# Extruder.net
KiCad netlist of a schematic drawn in Altium Designer
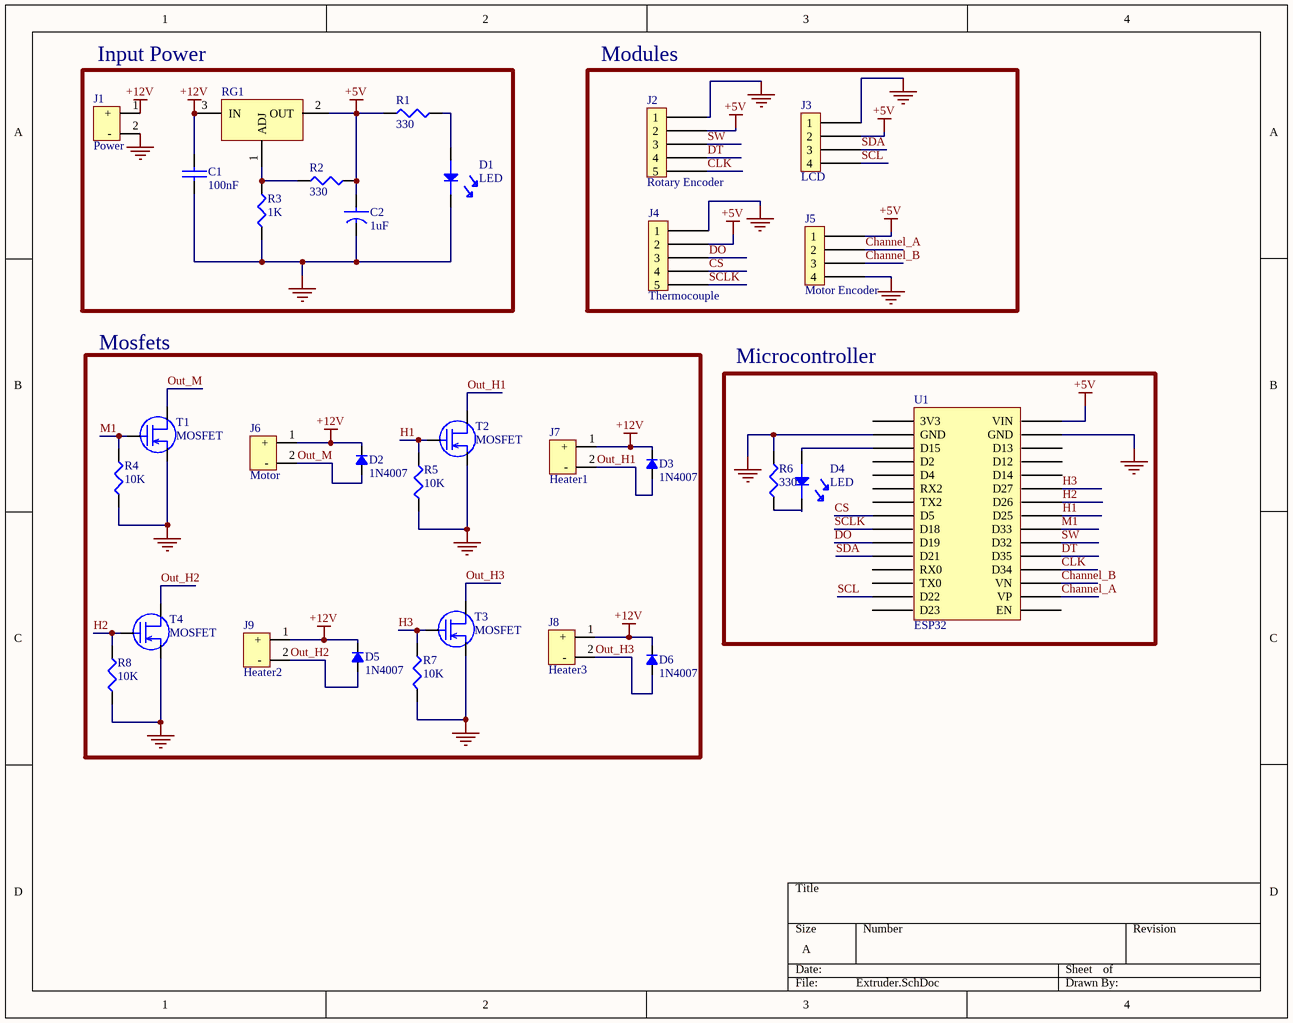
[diagram p0: Extruder.SchDoc]

(export (version "E")
  (design (tool "Eeschema 10.0.6"))
  (components
    (comp (ref "C1") (value "100nF") (footprint "CAP non") (libsource (lib "yehia") (part "Cap non")))
    (comp (ref "C2") (value "1uF") (footprint "CAP  pol") (libsource (lib "yehia") (part "Cap pol")))
    (comp (ref "D1") (value "LED") (footprint "LED-05 R") (libsource (lib "yehia") (part "LED")))
    (comp (ref "D2") (value "1N4007") (footprint "DO-41") (libsource (lib "yehia") (part "Diode")))
    (comp (ref "D3") (value "1N4007") (footprint "DO-41") (libsource (lib "yehia") (part "Diode")))
    (comp (ref "D4") (value "LED") (footprint "LED-05 R") (libsource (lib "yehia") (part "LED")))
    (comp (ref "D5") (value "1N4007") (footprint "DO-41") (libsource (lib "yehia") (part "Diode")))
    (comp (ref "D6") (value "1N4007") (footprint "DO-41") (libsource (lib "yehia") (part "Diode")))
    (comp (ref "J1")
      (value "Power")
      (footprint "CON")
      (description "Conn Terminal Blocks 2 POS 5mm Solder ST Thru-Hole 16A")
      (fields (field (name "VOLTAGE") "300V"))
      (libsource (lib "yehia") (part "1935161"))
    )
    (comp (ref "J2")
      (value "Rotary Encoder")
      (footprint "Data Connnector 5 pins")
      (libsource (lib "yehia") (part "Data Connector 5 pins"))
    )
    (comp (ref "J3")
      (value "LCD")
      (footprint "Data Connnector 4 pins")
      (libsource (lib "yehia") (part "Data Connector 4 pin"))
    )
    (comp (ref "J4")
      (value "Thermocouple")
      (footprint "Data Connnector 5 pins")
      (libsource (lib "yehia") (part "Data Connector 5 pins"))
    )
    (comp (ref "J5")
      (value "Motor Encoder")
      (footprint "Data Connnector 4 pins")
      (libsource (lib "yehia") (part "Data Connector 4 pin"))
    )
    (comp (ref "J6")
      (value "Motor")
      (footprint "CON")
      (description "Conn Terminal Blocks 2 POS 5mm Solder ST Thru-Hole 16A")
      (fields (field (name "VOLTAGE") "300V"))
      (libsource (lib "yehia") (part "1935161"))
    )
    (comp (ref "J7")
      (value "Heater1")
      (footprint "CON")
      (description "Conn Terminal Blocks 2 POS 5mm Solder ST Thru-Hole 16A")
      (fields (field (name "VOLTAGE") "300V"))
      (libsource (lib "yehia") (part "1935161"))
    )
    (comp (ref "J8")
      (value "Heater3")
      (footprint "CON")
      (description "Conn Terminal Blocks 2 POS 5mm Solder ST Thru-Hole 16A")
      (fields (field (name "VOLTAGE") "300V"))
      (libsource (lib "yehia") (part "1935161"))
    )
    (comp (ref "J9")
      (value "Heater2")
      (footprint "CON")
      (description "Conn Terminal Blocks 2 POS 5mm Solder ST Thru-Hole 16A")
      (fields (field (name "VOLTAGE") "300V"))
      (libsource (lib "yehia") (part "1935161"))
    )
    (comp (ref "R1") (value "330") (footprint "Resistor") (libsource (lib "yehia") (part "Resistor")))
    (comp (ref "R2") (value "330") (footprint "Resistor") (libsource (lib "yehia") (part "Resistor")))
    (comp (ref "R3") (value "1K") (footprint "Resistor") (libsource (lib "yehia") (part "Resistor")))
    (comp (ref "R4") (value "10K") (footprint "Resistor") (libsource (lib "yehia") (part "Resistor")))
    (comp (ref "R5") (value "10K") (footprint "Resistor") (libsource (lib "yehia") (part "Resistor")))
    (comp (ref "R6") (value "330") (footprint "Resistor") (libsource (lib "yehia") (part "Resistor")))
    (comp (ref "R7") (value "10K") (footprint "Resistor") (libsource (lib "yehia") (part "Resistor")))
    (comp (ref "R8") (value "10K") (footprint "Resistor") (libsource (lib "yehia") (part "Resistor")))
    (comp (ref "RG1")
      (value "Adjustable Voltage Regulator")
      (footprint "Regulator")
      (libsource (lib "yehia") (part "LM350"))
    )
    (comp (ref "T1") (value "MOSFET") (footprint "IRF540") (libsource (lib "yehia") (part "IRF540")))
    (comp (ref "T2") (value "MOSFET") (footprint "IRF540") (libsource (lib "yehia") (part "IRF540")))
    (comp (ref "T3") (value "MOSFET") (footprint "IRF540") (libsource (lib "yehia") (part "IRF540")))
    (comp (ref "T4") (value "MOSFET") (footprint "IRF540") (libsource (lib "yehia") (part "IRF540")))
    (comp (ref "U1") (value "ESP32") (footprint "ESP32") (libsource (lib "yehia") (part "ESP32")))
  )
  (nets
    (net (code "1") (name "+5V") (class "Default")
      (node (ref "C2") (pin "1") (pinfunction "1_1") (pintype "passive"))
      (node (ref "J2") (pin "2") (pinfunction "2_2") (pintype "passive"))
      (node (ref "J3") (pin "2") (pinfunction "2_2") (pintype "passive"))
      (node (ref "J4") (pin "2") (pinfunction "2_2") (pintype "passive"))
      (node (ref "J5") (pin "1") (pinfunction "1_1") (pintype "passive"))
      (node (ref "R1") (pin "2") (pinfunction "2_2") (pintype "passive"))
      (node (ref "R2") (pin "1") (pinfunction "1_1") (pintype "passive"))
      (node (ref "RG1") (pin "2") (pinfunction "OUT_2") (pintype "passive"))
      (node (ref "U1") (pin "30") (pinfunction "VIN_30") (pintype "passive"))
    )
    (net (code "2") (name "+12V") (class "Default")
      (node (ref "C1") (pin "1") (pinfunction "1_1") (pintype "passive"))
      (node (ref "D2") (pin "2") (pinfunction "2_2") (pintype "passive"))
      (node (ref "D3") (pin "2") (pinfunction "2_2") (pintype "passive"))
      (node (ref "D5") (pin "2") (pinfunction "2_2") (pintype "passive"))
      (node (ref "D6") (pin "2") (pinfunction "2_2") (pintype "passive"))
      (node (ref "J1") (pin "1") (pinfunction "+_1") (pintype "passive"))
      (node (ref "J6") (pin "1") (pinfunction "+_1") (pintype "passive"))
      (node (ref "J7") (pin "1") (pinfunction "+_1") (pintype "passive"))
      (node (ref "J8") (pin "1") (pinfunction "+_1") (pintype "passive"))
      (node (ref "J9") (pin "1") (pinfunction "+_1") (pintype "passive"))
      (node (ref "RG1") (pin "3") (pinfunction "IN_3") (pintype "passive"))
    )
    (net (code "3") (name "/CLK") (class "Default")
      (node (ref "J2") (pin "5") (pinfunction "5_5") (pintype "passive"))
      (node (ref "U1") (pin "19") (pinfunction "D34_19") (pintype "passive"))
    )
    (net (code "4") (name "/CS") (class "Default")
      (node (ref "J4") (pin "4") (pinfunction "4_4") (pintype "passive"))
      (node (ref "U1") (pin "8") (pinfunction "D5_8") (pintype "passive"))
    )
    (net (code "5") (name "/Channel_A") (class "Default")
      (node (ref "J5") (pin "2") (pinfunction "2_2") (pintype "passive"))
      (node (ref "U1") (pin "17") (pinfunction "VP_17") (pintype "passive"))
    )
    (net (code "6") (name "/Channel_B") (class "Default")
      (node (ref "J5") (pin "3") (pinfunction "3_3") (pintype "passive"))
      (node (ref "U1") (pin "18") (pinfunction "VN_18") (pintype "passive"))
    )
    (net (code "7") (name "/DO") (class "Default")
      (node (ref "J4") (pin "3") (pinfunction "3_3") (pintype "passive"))
      (node (ref "U1") (pin "10") (pinfunction "D19_10") (pintype "passive"))
    )
    (net (code "8") (name "/DT") (class "Default")
      (node (ref "J2") (pin "4") (pinfunction "4_4") (pintype "passive"))
      (node (ref "U1") (pin "20") (pinfunction "D35_20") (pintype "passive"))
    )
    (net (code "9") (name "/H1") (class "Default")
      (node (ref "R5") (pin "2") (pinfunction "2_2") (pintype "passive"))
      (node (ref "T2") (pin "1") (pinfunction "Gate_1") (pintype "passive"))
      (node (ref "U1") (pin "23") (pinfunction "D25_23") (pintype "passive"))
    )
    (net (code "10") (name "/H2") (class "Default")
      (node (ref "R8") (pin "2") (pinfunction "2_2") (pintype "passive"))
      (node (ref "T4") (pin "1") (pinfunction "Gate_1") (pintype "passive"))
      (node (ref "U1") (pin "24") (pinfunction "D26_24") (pintype "passive"))
    )
    (net (code "11") (name "/H3") (class "Default")
      (node (ref "R7") (pin "2") (pinfunction "2_2") (pintype "passive"))
      (node (ref "T3") (pin "1") (pinfunction "Gate_1") (pintype "passive"))
      (node (ref "U1") (pin "25") (pinfunction "D27_25") (pintype "passive"))
    )
    (net (code "12") (name "/M1") (class "Default")
      (node (ref "R4") (pin "2") (pinfunction "2_2") (pintype "passive"))
      (node (ref "T1") (pin "1") (pinfunction "Gate_1") (pintype "passive"))
      (node (ref "U1") (pin "22") (pinfunction "D33_22") (pintype "passive"))
    )
    (net (code "13") (name "/Out_H1") (class "Default")
      (node (ref "D3") (pin "1") (pinfunction "1_1") (pintype "passive"))
      (node (ref "J7") (pin "2") (pinfunction "-_2") (pintype "passive"))
      (node (ref "T2") (pin "2") (pinfunction "Drain_2") (pintype "passive"))
    )
    (net (code "14") (name "/Out_H2") (class "Default")
      (node (ref "D5") (pin "1") (pinfunction "1_1") (pintype "passive"))
      (node (ref "J9") (pin "2") (pinfunction "-_2") (pintype "passive"))
      (node (ref "T4") (pin "2") (pinfunction "Drain_2") (pintype "passive"))
    )
    (net (code "15") (name "/Out_H3") (class "Default")
      (node (ref "D6") (pin "1") (pinfunction "1_1") (pintype "passive"))
      (node (ref "J8") (pin "2") (pinfunction "-_2") (pintype "passive"))
      (node (ref "T3") (pin "2") (pinfunction "Drain_2") (pintype "passive"))
    )
    (net (code "16") (name "/Out_M") (class "Default")
      (node (ref "D2") (pin "1") (pinfunction "1_1") (pintype "passive"))
      (node (ref "J6") (pin "2") (pinfunction "-_2") (pintype "passive"))
      (node (ref "T1") (pin "2") (pinfunction "Drain_2") (pintype "passive"))
    )
    (net (code "17") (name "/SCL") (class "Default")
      (node (ref "J3") (pin "4") (pinfunction "4_4") (pintype "passive"))
      (node (ref "U1") (pin "14") (pinfunction "D22_14") (pintype "passive"))
    )
    (net (code "18") (name "/SCLK") (class "Default")
      (node (ref "J4") (pin "5") (pinfunction "5_5") (pintype "passive"))
      (node (ref "U1") (pin "9") (pinfunction "D18_9") (pintype "passive"))
    )
    (net (code "19") (name "/SDA") (class "Default")
      (node (ref "J3") (pin "3") (pinfunction "3_3") (pintype "passive"))
      (node (ref "U1") (pin "11") (pinfunction "D21_11") (pintype "passive"))
    )
    (net (code "20") (name "/SW") (class "Default")
      (node (ref "J2") (pin "3") (pinfunction "3_3") (pintype "passive"))
      (node (ref "U1") (pin "21") (pinfunction "D32_21") (pintype "passive"))
    )
    (net (code "21") (name "GND") (class "Default")
      (node (ref "C1") (pin "2") (pinfunction "2_2") (pintype "passive"))
      (node (ref "C2") (pin "2") (pinfunction "2_2") (pintype "passive"))
      (node (ref "D1") (pin "1") (pinfunction "Cathode_1") (pintype "passive"))
      (node (ref "J1") (pin "2") (pinfunction "-_2") (pintype "passive"))
      (node (ref "J2") (pin "1") (pinfunction "1_1") (pintype "passive"))
      (node (ref "J3") (pin "1") (pinfunction "1_1") (pintype "passive"))
      (node (ref "J4") (pin "1") (pinfunction "1_1") (pintype "passive"))
      (node (ref "J5") (pin "4") (pinfunction "4_4") (pintype "passive"))
      (node (ref "R3") (pin "1") (pinfunction "1_1") (pintype "passive"))
      (node (ref "R4") (pin "1") (pinfunction "1_1") (pintype "passive"))
      (node (ref "R5") (pin "1") (pinfunction "1_1") (pintype "passive"))
      (node (ref "R6") (pin "1") (pinfunction "1_1") (pintype "passive"))
      (node (ref "R7") (pin "1") (pinfunction "1_1") (pintype "passive"))
      (node (ref "R8") (pin "1") (pinfunction "1_1") (pintype "passive"))
      (node (ref "T1") (pin "3") (pinfunction "Source_3") (pintype "passive"))
      (node (ref "T2") (pin "3") (pinfunction "Source_3") (pintype "passive"))
      (node (ref "T3") (pin "3") (pinfunction "Source_3") (pintype "passive"))
      (node (ref "T4") (pin "3") (pinfunction "Source_3") (pintype "passive"))
      (node (ref "U1") (pin "2") (pinfunction "GND_2") (pintype "passive"))
      (node (ref "U1") (pin "29") (pinfunction "GND_29") (pintype "passive"))
    )
    (net (code "22") (name "Net-(D1-Anode)") (class "Default")
      (node (ref "D1") (pin "2") (pinfunction "Anode_2") (pintype "passive"))
      (node (ref "R1") (pin "1") (pinfunction "1_1") (pintype "passive"))
    )
    (net (code "23") (name "Net-(D4-Anode)") (class "Default")
      (node (ref "D4") (pin "2") (pinfunction "Anode_2") (pintype "passive"))
      (node (ref "U1") (pin "3") (pinfunction "D15_3") (pintype "passive"))
    )
    (net (code "24") (name "Net-(D4-Cathode)") (class "Default")
      (node (ref "D4") (pin "1") (pinfunction "Cathode_1") (pintype "passive"))
      (node (ref "R6") (pin "2") (pinfunction "2_2") (pintype "passive"))
    )
    (net (code "25") (name "Net-(RG1-ADJ)") (class "Default")
      (node (ref "R2") (pin "2") (pinfunction "2_2") (pintype "passive"))
      (node (ref "R3") (pin "2") (pinfunction "2_2") (pintype "passive"))
      (node (ref "RG1") (pin "1") (pinfunction "ADJ_1") (pintype "passive"))
    )
    (net (code "26") (name "unconnected-(U1-3V3-Pad1)") (class "Default")
      (node (ref "U1") (pin "1") (pinfunction "3V3_1") (pintype "passive"))
    )
    (net (code "27") (name "unconnected-(U1-D2-Pad4)") (class "Default")
      (node (ref "U1") (pin "4") (pinfunction "D2_4") (pintype "passive"))
    )
    (net (code "28") (name "unconnected-(U1-D4-Pad5)") (class "Default")
      (node (ref "U1") (pin "5") (pinfunction "D4_5") (pintype "passive"))
    )
    (net (code "29") (name "unconnected-(U1-D12-Pad27)") (class "Default")
      (node (ref "U1") (pin "27") (pinfunction "D12_27") (pintype "passive"))
    )
    (net (code "30") (name "unconnected-(U1-D13-Pad28)") (class "Default")
      (node (ref "U1") (pin "28") (pinfunction "D13_28") (pintype "passive"))
    )
    (net (code "31") (name "unconnected-(U1-D14-Pad26)") (class "Default")
      (node (ref "U1") (pin "26") (pinfunction "D14_26") (pintype "passive"))
    )
    (net (code "32") (name "unconnected-(U1-D23-Pad15)") (class "Default")
      (node (ref "U1") (pin "15") (pinfunction "D23_15") (pintype "passive"))
    )
    (net (code "33") (name "unconnected-(U1-EN-Pad16)") (class "Default")
      (node (ref "U1") (pin "16") (pinfunction "EN_16") (pintype "passive"))
    )
    (net (code "34") (name "unconnected-(U1-RX0-Pad12)") (class "Default")
      (node (ref "U1") (pin "12") (pinfunction "RX0_12") (pintype "passive"))
    )
    (net (code "35") (name "unconnected-(U1-RX2-Pad6)") (class "Default")
      (node (ref "U1") (pin "6") (pinfunction "RX2_6") (pintype "passive"))
    )
    (net (code "36") (name "unconnected-(U1-TX0-Pad13)") (class "Default")
      (node (ref "U1") (pin "13") (pinfunction "TX0_13") (pintype "passive"))
    )
    (net (code "37") (name "unconnected-(U1-TX2-Pad7)") (class "Default")
      (node (ref "U1") (pin "7") (pinfunction "TX2_7") (pintype "passive"))
    )
  )
)
